# LOCAL_PWR.net
KiCad netlist of a schematic drawn in Altium Designer
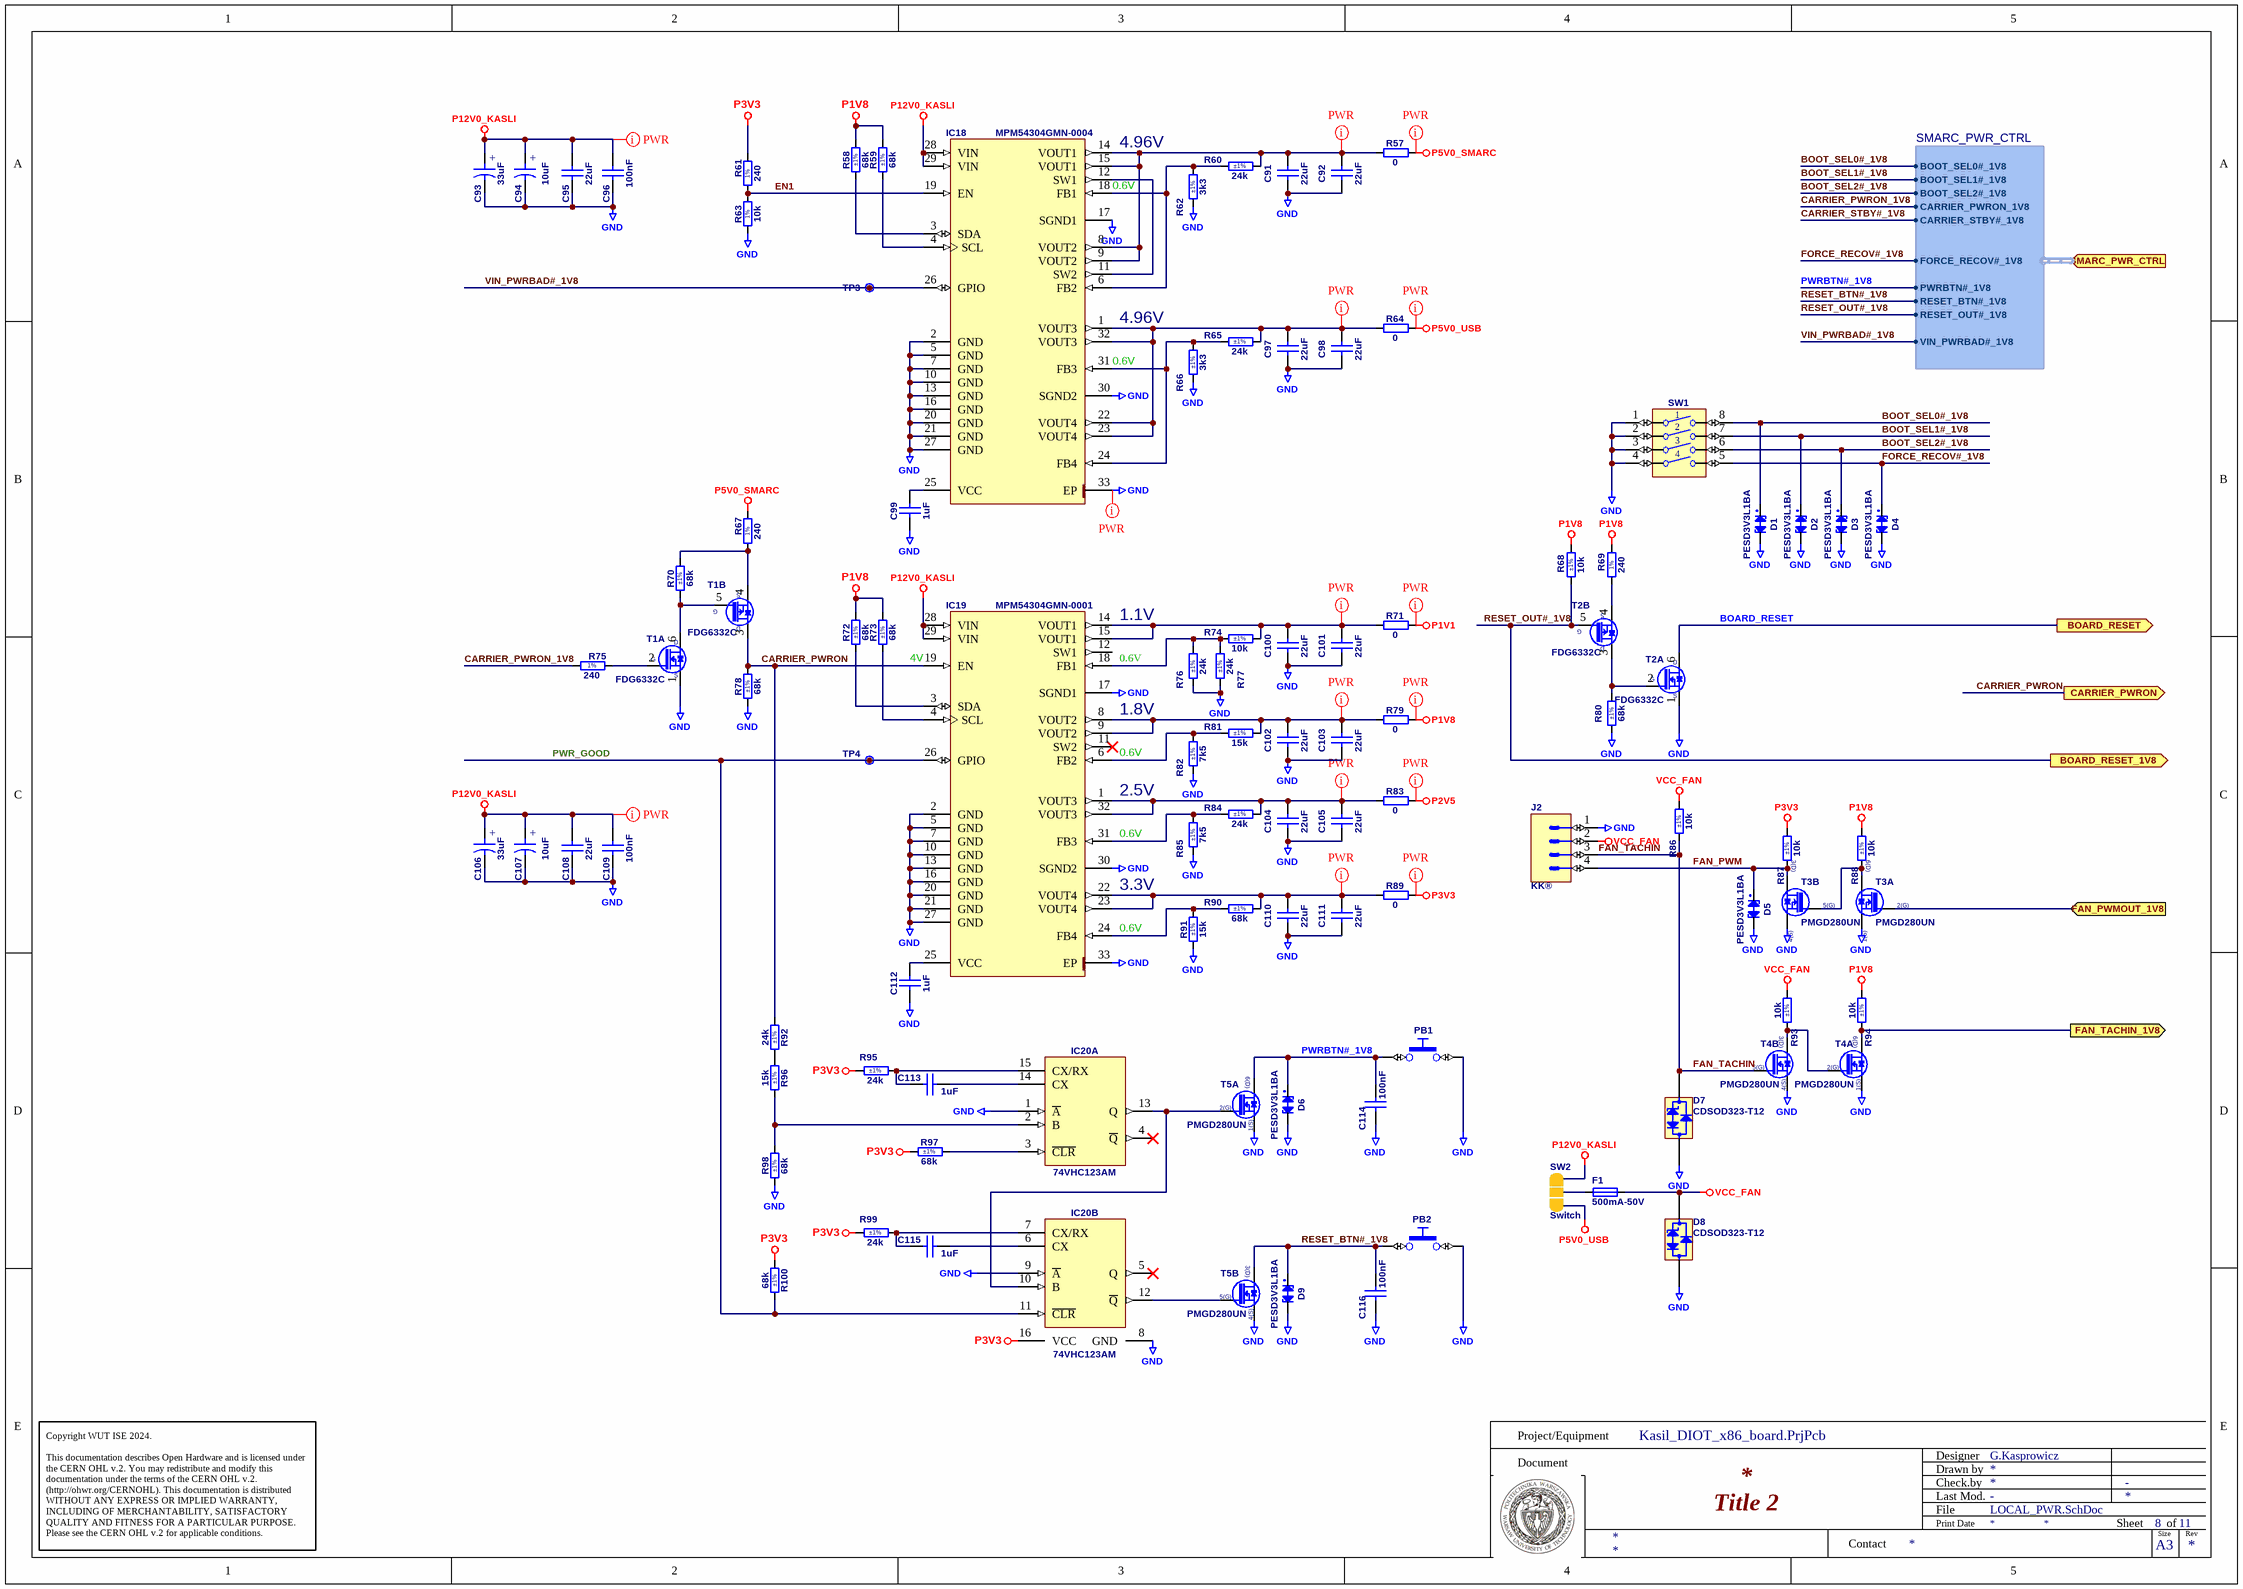
[diagram p0: LOCAL_PWR.SchDoc]

(export (version "E")
  (design (tool "Eeschema 10.0.6"))
  (components
    (comp (ref "C91")
      (value "22uF")
      (footprint "CAPC2012X135N")
      (description "Non-polarised capacitor")
      (fields
        (field (name "MANUFACTURER PART NUMBER") "CC0805_22UF_16V_10%_X5R")
        (field (name "MANUFACTURER") "GENERIC")
        (field (name "AUTHOR") "CERN DEM JLC")
      )
      (libsource (lib "Capacitors") (part "Capacitor - non polarized"))
    )
    (comp (ref "C92")
      (value "22uF")
      (footprint "CAPC2012X135N")
      (description "Non-polarised capacitor")
      (fields
        (field (name "MANUFACTURER PART NUMBER") "CC0805_22UF_16V_10%_X5R")
        (field (name "MANUFACTURER") "GENERIC")
        (field (name "AUTHOR") "CERN DEM JLC")
      )
      (libsource (lib "Capacitors") (part "Capacitor - non polarized"))
    )
    (comp (ref "C93")
      (value "33uF")
      (footprint "CAPMP3528X210N")
      (description "Polarised capacitor")
      (fields
        (field (name "PART NUMBER") "CTE3528-21_33UF_16V_10%")
        (field (name "VOLTAGE") "16V")
        (field (name "AUTHOR") "CERN DEM JLC")
      )
      (libsource (lib "Capacitors") (part "Capacitor - polarized"))
    )
    (comp (ref "C94")
      (value "10uF")
      (footprint "CAPMP3216X180N")
      (description "Polarised capacitor")
      (fields
        (field (name "PART NUMBER") "CTE3216-18_10UF_16V_20%_AVX_TCJ")
        (field (name "VOLTAGE") "16V")
        (field (name "AUTHOR") "CERN DEM JLC")
      )
      (libsource (lib "Capacitors") (part "Capacitor - polarized"))
    )
    (comp (ref "C95")
      (value "22uF")
      (footprint "CAPC2012X135N")
      (description "Non-polarised capacitor")
      (fields
        (field (name "MANUFACTURER PART NUMBER") "CC0805_22UF_16V_10%_X5R")
        (field (name "MANUFACTURER") "GENERIC")
        (field (name "AUTHOR") "CERN DEM JLC")
      )
      (libsource (lib "Capacitors") (part "Capacitor - non polarized"))
    )
    (comp (ref "C96")
      (value "100nF")
      (footprint "CAPC1005X55N")
      (description "Non-polarised capacitor")
      (fields
        (field (name "PART NUMBER") "CC0402_100NF_16V_10%_X7R")
        (field (name "VOLTAGE") "16V")
        (field (name "AUTHOR") "CERN DEM JLC")
      )
      (libsource (lib "Capacitors") (part "Capacitor - non polarized"))
    )
    (comp (ref "C97")
      (value "22uF")
      (footprint "CAPC2012X135N")
      (description "Non-polarised capacitor")
      (fields
        (field (name "MANUFACTURER PART NUMBER") "CC0805_22UF_16V_10%_X5R")
        (field (name "MANUFACTURER") "GENERIC")
        (field (name "AUTHOR") "CERN DEM JLC")
      )
      (libsource (lib "Capacitors") (part "Capacitor - non polarized"))
    )
    (comp (ref "C98")
      (value "22uF")
      (footprint "CAPC2012X135N")
      (description "Non-polarised capacitor")
      (fields
        (field (name "MANUFACTURER PART NUMBER") "CC0805_22UF_16V_10%_X5R")
        (field (name "MANUFACTURER") "GENERIC")
        (field (name "AUTHOR") "CERN DEM JLC")
      )
      (libsource (lib "Capacitors") (part "Capacitor - non polarized"))
    )
    (comp (ref "C99")
      (value "1uF")
      (footprint "CAPC1005X55N")
      (description "Non-polarised capacitor")
      (fields
        (field (name "PART NUMBER") "CC0402_1UF_16V_10%_X5R")
        (field (name "VOLTAGE") "16V")
        (field (name "AUTHOR") "CERN DEM JLC")
      )
      (libsource (lib "Capacitors") (part "Capacitor - non polarized"))
    )
    (comp (ref "C100")
      (value "22uF")
      (footprint "CAPC2012X135N")
      (description "Non-polarised capacitor")
      (fields
        (field (name "MANUFACTURER PART NUMBER") "CC0805_22UF_16V_10%_X5R")
        (field (name "MANUFACTURER") "GENERIC")
        (field (name "AUTHOR") "CERN DEM JLC")
      )
      (libsource (lib "Capacitors") (part "Capacitor - non polarized"))
    )
    (comp (ref "C101")
      (value "22uF")
      (footprint "CAPC2012X135N")
      (description "Non-polarised capacitor")
      (fields
        (field (name "MANUFACTURER PART NUMBER") "CC0805_22UF_16V_10%_X5R")
        (field (name "MANUFACTURER") "GENERIC")
        (field (name "AUTHOR") "CERN DEM JLC")
      )
      (libsource (lib "Capacitors") (part "Capacitor - non polarized"))
    )
    (comp (ref "C102")
      (value "22uF")
      (footprint "CAPC2012X135N")
      (description "Non-polarised capacitor")
      (fields
        (field (name "MANUFACTURER PART NUMBER") "CC0805_22UF_16V_10%_X5R")
        (field (name "MANUFACTURER") "GENERIC")
        (field (name "AUTHOR") "CERN DEM JLC")
      )
      (libsource (lib "Capacitors") (part "Capacitor - non polarized"))
    )
    (comp (ref "C103")
      (value "22uF")
      (footprint "CAPC2012X135N")
      (description "Non-polarised capacitor")
      (fields
        (field (name "MANUFACTURER PART NUMBER") "CC0805_22UF_16V_10%_X5R")
        (field (name "MANUFACTURER") "GENERIC")
        (field (name "AUTHOR") "CERN DEM JLC")
      )
      (libsource (lib "Capacitors") (part "Capacitor - non polarized"))
    )
    (comp (ref "C104")
      (value "22uF")
      (footprint "CAPC2012X135N")
      (description "Non-polarised capacitor")
      (fields
        (field (name "MANUFACTURER PART NUMBER") "CC0805_22UF_16V_10%_X5R")
        (field (name "MANUFACTURER") "GENERIC")
        (field (name "AUTHOR") "CERN DEM JLC")
      )
      (libsource (lib "Capacitors") (part "Capacitor - non polarized"))
    )
    (comp (ref "C105")
      (value "22uF")
      (footprint "CAPC2012X135N")
      (description "Non-polarised capacitor")
      (fields
        (field (name "MANUFACTURER PART NUMBER") "CC0805_22UF_16V_10%_X5R")
        (field (name "MANUFACTURER") "GENERIC")
        (field (name "AUTHOR") "CERN DEM JLC")
      )
      (libsource (lib "Capacitors") (part "Capacitor - non polarized"))
    )
    (comp (ref "C106")
      (value "33uF")
      (footprint "CAPMP3528X210N")
      (description "Polarised capacitor")
      (fields
        (field (name "PART NUMBER") "CTE3528-21_33UF_16V_10%")
        (field (name "VOLTAGE") "16V")
        (field (name "AUTHOR") "CERN DEM JLC")
      )
      (libsource (lib "Capacitors") (part "Capacitor - polarized"))
    )
    (comp (ref "C107")
      (value "10uF")
      (footprint "CAPMP3216X180N")
      (description "Polarised capacitor")
      (fields
        (field (name "PART NUMBER") "CTE3216-18_10UF_16V_20%_AVX_TCJ")
        (field (name "VOLTAGE") "16V")
        (field (name "AUTHOR") "CERN DEM JLC")
      )
      (libsource (lib "Capacitors") (part "Capacitor - polarized"))
    )
    (comp (ref "C108")
      (value "22uF")
      (footprint "CAPC2012X135N")
      (description "Non-polarised capacitor")
      (fields
        (field (name "MANUFACTURER PART NUMBER") "CC0805_22UF_16V_10%_X5R")
        (field (name "MANUFACTURER") "GENERIC")
        (field (name "AUTHOR") "CERN DEM JLC")
      )
      (libsource (lib "Capacitors") (part "Capacitor - non polarized"))
    )
    (comp (ref "C109")
      (value "100nF")
      (footprint "CAPC1005X55N")
      (description "Non-polarised capacitor")
      (fields
        (field (name "PART NUMBER") "CC0402_100NF_16V_10%_X7R")
        (field (name "VOLTAGE") "16V")
        (field (name "AUTHOR") "CERN DEM JLC")
      )
      (libsource (lib "Capacitors") (part "Capacitor - non polarized"))
    )
    (comp (ref "C110")
      (value "22uF")
      (footprint "CAPC2012X135N")
      (description "Non-polarised capacitor")
      (fields
        (field (name "MANUFACTURER PART NUMBER") "CC0805_22UF_16V_10%_X5R")
        (field (name "MANUFACTURER") "GENERIC")
        (field (name "AUTHOR") "CERN DEM JLC")
      )
      (libsource (lib "Capacitors") (part "Capacitor - non polarized"))
    )
    (comp (ref "C111")
      (value "22uF")
      (footprint "CAPC2012X135N")
      (description "Non-polarised capacitor")
      (fields
        (field (name "MANUFACTURER PART NUMBER") "CC0805_22UF_16V_10%_X5R")
        (field (name "MANUFACTURER") "GENERIC")
        (field (name "AUTHOR") "CERN DEM JLC")
      )
      (libsource (lib "Capacitors") (part "Capacitor - non polarized"))
    )
    (comp (ref "C112")
      (value "1uF")
      (footprint "CAPC1005X55N")
      (description "Non-polarised capacitor")
      (fields
        (field (name "PART NUMBER") "CC0402_1UF_16V_10%_X5R")
        (field (name "VOLTAGE") "16V")
        (field (name "AUTHOR") "CERN DEM JLC")
      )
      (libsource (lib "Capacitors") (part "Capacitor - non polarized"))
    )
    (comp (ref "C113")
      (value "1uF")
      (footprint "CAPC1005X55N")
      (description "Non-polarised capacitor")
      (fields
        (field (name "PART NUMBER") "CC0402_1UF_16V_10%_X5R")
        (field (name "VOLTAGE") "16V")
        (field (name "AUTHOR") "CERN DEM JLC")
      )
      (libsource (lib "Capacitors") (part "Capacitor - non polarized"))
    )
    (comp (ref "C114")
      (value "100nF")
      (footprint "CAPC1005X55N")
      (description "Non-polarised capacitor")
      (fields
        (field (name "PART NUMBER") "CC0402_100NF_16V_10%_X7R")
        (field (name "VOLTAGE") "16V")
        (field (name "AUTHOR") "CERN DEM JLC")
      )
      (libsource (lib "Capacitors") (part "Capacitor - non polarized"))
    )
    (comp (ref "C115")
      (value "1uF")
      (footprint "CAPC1005X55N")
      (description "Non-polarised capacitor")
      (fields
        (field (name "PART NUMBER") "CC0402_1UF_16V_10%_X5R")
        (field (name "VOLTAGE") "16V")
        (field (name "AUTHOR") "CERN DEM JLC")
      )
      (libsource (lib "Capacitors") (part "Capacitor - non polarized"))
    )
    (comp (ref "C116")
      (value "100nF")
      (footprint "CAPC1005X55N")
      (description "Non-polarised capacitor")
      (fields
        (field (name "PART NUMBER") "CC0402_100NF_16V_10%_X7R")
        (field (name "VOLTAGE") "16V")
        (field (name "AUTHOR") "CERN DEM JLC")
      )
      (libsource (lib "Capacitors") (part "Capacitor - non polarized"))
    )
    (comp (ref "D1")
      (value "PESD3V3L1BA")
      (footprint "SOD2512X110N")
      (description "Bi-Directional ESD Protection Diode")
      (fields
        (field (name "VOLTAGE") "3V3")
        (field (name "POWER") "500W")
        (field (name "AUTHOR") "CERN DEM JMW")
      )
      (libsource (lib "ICs And Semiconductors") (part "Diode ESD Bi-Directional Dot"))
    )
    (comp (ref "D2")
      (value "PESD3V3L1BA")
      (footprint "SOD2512X110N")
      (description "Bi-Directional ESD Protection Diode")
      (fields
        (field (name "VOLTAGE") "3V3")
        (field (name "POWER") "500W")
        (field (name "AUTHOR") "CERN DEM JMW")
      )
      (libsource (lib "ICs And Semiconductors") (part "Diode ESD Bi-Directional Dot"))
    )
    (comp (ref "D3")
      (value "PESD3V3L1BA")
      (footprint "SOD2512X110N")
      (description "Bi-Directional ESD Protection Diode")
      (fields
        (field (name "VOLTAGE") "3V3")
        (field (name "POWER") "500W")
        (field (name "AUTHOR") "CERN DEM JMW")
      )
      (libsource (lib "ICs And Semiconductors") (part "Diode ESD Bi-Directional Dot"))
    )
    (comp (ref "D4")
      (value "PESD3V3L1BA")
      (footprint "SOD2512X110N")
      (description "Bi-Directional ESD Protection Diode")
      (fields
        (field (name "VOLTAGE") "3V3")
        (field (name "POWER") "500W")
        (field (name "AUTHOR") "CERN DEM JMW")
      )
      (libsource (lib "ICs And Semiconductors") (part "Diode ESD Bi-Directional Dot"))
    )
    (comp (ref "D5")
      (value "PESD3V3L1BA")
      (footprint "SOD2512X110N")
      (description "Bi-Directional ESD Protection Diode")
      (fields
        (field (name "VOLTAGE") "3V3")
        (field (name "POWER") "500W")
        (field (name "AUTHOR") "CERN DEM JMW")
      )
      (libsource (lib "ICs And Semiconductors") (part "Diode ESD Bi-Directional Dot"))
    )
    (comp (ref "D6")
      (value "PESD3V3L1BA")
      (footprint "SOD2512X110N")
      (description "Bi-Directional ESD Protection Diode")
      (fields
        (field (name "VOLTAGE") "3V3")
        (field (name "POWER") "500W")
        (field (name "AUTHOR") "CERN DEM JMW")
      )
      (libsource (lib "ICs And Semiconductors") (part "Diode ESD Bi-Directional Dot"))
    )
    (comp (ref "D7")
      (value "CDSOD323-T12")
      (footprint "SOD2513X114N")
      (description "Unidirectional ESD Protection for Transient Voltage Suppressor Diode")
      (fields
        (field (name "VOLTAGE") "12V")
        (field (name "POWER") "350W")
        (field (name "AUTHOR") "CERN DEM BC")
      )
      (libsource (lib "ICs And Semiconductors") (part "CDSOD323-TXX"))
    )
    (comp (ref "D8")
      (value "CDSOD323-T12")
      (footprint "SOD2513X114N")
      (description "Unidirectional ESD Protection for Transient Voltage Suppressor Diode")
      (fields
        (field (name "VOLTAGE") "12V")
        (field (name "POWER") "350W")
        (field (name "AUTHOR") "CERN DEM BC")
      )
      (libsource (lib "ICs And Semiconductors") (part "CDSOD323-TXX"))
    )
    (comp (ref "D9")
      (value "PESD3V3L1BA")
      (footprint "SOD2512X110N")
      (description "Bi-Directional ESD Protection Diode")
      (fields
        (field (name "VOLTAGE") "3V3")
        (field (name "POWER") "500W")
        (field (name "AUTHOR") "CERN DEM JMW")
      )
      (libsource (lib "ICs And Semiconductors") (part "Diode ESD Bi-Directional Dot"))
    )
    (comp (ref "F1")
      (value "500mA-50V")
      (footprint "FUSC_BOURNS_SF-0603F")
      (description "Fuse")
      (fields
        (field (name "PART NUMBER") "FUS0603_BOURNS-SF-0603F050-2")
        (field (name "MANUFACTURER") "BOURNS")
        (field (name "AUTHOR") "CERN DEM JLC")
      )
      (libsource (lib "Eletro-mechanical") (part "Fuse"))
    )
    (comp (ref "IC18")
      (value "MPM54304GMN-0004")
      (footprint "MPS_MPM54304GMN")
      (description "Quad-Output Power Module with I2C and MTP")
      (fields
        (field (name "PART NUMBER") "MPM54304GMN-002")
        (field (name "MANUFACTURER") "MPS (MONOLITIC  POWER SYSTEMS)")
        (field (name "AUTHOR") "CERN DEM BC")
      )
      (libsource (lib "ICs And Semiconductors") (part "MPM54304GMN"))
    )
    (comp (ref "IC19")
      (value "MPM54304GMN-0001")
      (footprint "MPS_MPM54304GMN")
      (description "Quad-Output Power Module with I2C and MTP")
      (fields
        (field (name "MANUFACTURER") "MPS (MONOLITIC  POWER SYSTEMS)")
        (field (name "MANUFACTURER PART NUMBER") "MPM54304GMN-002")
        (field (name "AUTHOR") "CERN DEM BC")
      )
      (libsource (lib "ICs And Semiconductors") (part "MPM54304GMN"))
    )
    (comp (ref "IC20")
      (value "74VHC123AM")
      (footprint "SOIC127P600X175-16N")
      (description "Retriggerable Monostable Multivibrator")
      (fields (field (name "MANUFACTURER") "FAIRCHILD SEMICONDUCTOR") (field (name "AUTHOR") "CERN DEM BC"))
      (libsource (lib "ICs And Semiconductors") (part "74123"))
    )
    (comp (ref "J2")
      (value "KK®")
      (footprint "MOLEX_22-04-1041")
      (description "Connector 4 Male")
      (fields
        (field (name "PART NUMBER") "MOLEX_22-04-1041")
        (field (name "MANUFACTURER") "MOLEX")
        (field (name "AUTHOR") "CERN DEM JLC")
      )
      (libsource (lib "Connectors") (part "Connector 4 Male"))
    )
    (comp (ref "PB1")
      (value "Push Button")
      (footprint "PB_TYCO_FSMSM")
      (description "Push-Button Switch SPST")
      (fields
        (field (name "PART NUMBER") "PB_TYCO_FSMSM")
        (field (name "MANUFACTURER") "TYCO ELECTRONICS")
        (field (name "AUTHOR") "CERN DEM JLC")
      )
      (libsource (lib "Eletro-mechanical") (part "PB SPST 1NO-2NO"))
    )
    (comp (ref "PB2")
      (value "Push Button")
      (footprint "PB_TYCO_FSMSM")
      (description "Push-Button Switch SPST")
      (fields
        (field (name "PART NUMBER") "PB_TYCO_FSMSM")
        (field (name "MANUFACTURER") "TYCO ELECTRONICS")
        (field (name "AUTHOR") "CERN DEM JLC")
      )
      (libsource (lib "Eletro-mechanical") (part "PB SPST 1NO-2NO"))
    )
    (comp (ref "R57")
      (value "0")
      (footprint "RESC2012X60N")
      (description "Resistor")
      (fields
        (field (name "PART NUMBER") "R0805_0R_JUMPER")
        (field (name "MANUFACTURER") "GENERIC")
        (field (name "AUTHOR") "CERN DEM JLC")
      )
      (libsource (lib "Resistors") (part "Resistor"))
    )
    (comp (ref "R58")
      (value "68k")
      (footprint "RESC1005X40N")
      (description "Resistor - 1%")
      (fields
        (field (name "TOLERANCE") "±1%")
        (field (name "PART NUMBER") "R0402_68K_1%_0.0625W_100PPM")
        (field (name "POWER") "0.0625W")
        (field (name "AUTHOR") "CERN DEM JLC")
      )
      (libsource (lib "Resistors") (part "Resistor - 1%"))
    )
    (comp (ref "R59")
      (value "68k")
      (footprint "RESC1005X40N")
      (description "Resistor - 1%")
      (fields
        (field (name "TOLERANCE") "±1%")
        (field (name "PART NUMBER") "R0402_68K_1%_0.0625W_100PPM")
        (field (name "POWER") "0.0625W")
        (field (name "AUTHOR") "CERN DEM JLC")
      )
      (libsource (lib "Resistors") (part "Resistor - 1%"))
    )
    (comp (ref "R60")
      (value "24k")
      (footprint "RESC1005X40N")
      (description "Resistor - 1%")
      (fields
        (field (name "TOLERANCE") "±1%")
        (field (name "PART NUMBER") "R0402_24K_1%_0.0625W_100PPM")
        (field (name "POWER") "0.0625W")
        (field (name "AUTHOR") "CERN DEM JLC")
      )
      (libsource (lib "Resistors") (part "Resistor - 1%"))
    )
    (comp (ref "R61")
      (value "240")
      (footprint "RESC1005X40N")
      (description "Resistor - 1%")
      (fields
        (field (name "PART NUMBER") "R0402_240R_1%_0.0625W_100PPM")
        (field (name "POWER") "0.0625W")
        (field (name "AUTHOR") "CERN DEM JLC")
      )
      (libsource (lib "Resistors") (part "Resistor - 1%"))
    )
    (comp (ref "R62")
      (value "3k3")
      (footprint "RESC1005X40N")
      (description "Resistor - 1%")
      (fields
        (field (name "TOLERANCE") "±1%")
        (field (name "PART NUMBER") "R0402_3K3_1%_0.0625W_100PPM")
        (field (name "POWER") "0.0625W")
        (field (name "AUTHOR") "CERN DEM JLC")
      )
      (libsource (lib "Resistors") (part "Resistor - 1%"))
    )
    (comp (ref "R63")
      (value "10k")
      (footprint "RESC1005X40N")
      (description "Resistor - 1%")
      (fields
        (field (name "PART NUMBER") "R0402_10K_1%_0.0625W_100PPM")
        (field (name "POWER") "0.0625W")
        (field (name "AUTHOR") "CERN DEM JLC")
      )
      (libsource (lib "Resistors") (part "Resistor - 1%"))
    )
    (comp (ref "R64")
      (value "0")
      (footprint "RESC2012X60N")
      (description "Resistor")
      (fields
        (field (name "PART NUMBER") "R0805_0R_JUMPER")
        (field (name "MANUFACTURER") "GENERIC")
        (field (name "AUTHOR") "CERN DEM JLC")
      )
      (libsource (lib "Resistors") (part "Resistor"))
    )
    (comp (ref "R65")
      (value "24k")
      (footprint "RESC1005X40N")
      (description "Resistor - 1%")
      (fields
        (field (name "TOLERANCE") "±1%")
        (field (name "PART NUMBER") "R0402_24K_1%_0.0625W_100PPM")
        (field (name "POWER") "0.0625W")
        (field (name "AUTHOR") "CERN DEM JLC")
      )
      (libsource (lib "Resistors") (part "Resistor - 1%"))
    )
    (comp (ref "R66")
      (value "3k3")
      (footprint "RESC1005X40N")
      (description "Resistor - 1%")
      (fields
        (field (name "TOLERANCE") "±1%")
        (field (name "PART NUMBER") "R0402_3K3_1%_0.0625W_100PPM")
        (field (name "POWER") "0.0625W")
        (field (name "AUTHOR") "CERN DEM JLC")
      )
      (libsource (lib "Resistors") (part "Resistor - 1%"))
    )
    (comp (ref "R67")
      (value "240")
      (footprint "RESC1005X40N")
      (description "Resistor - 1%")
      (fields
        (field (name "PART NUMBER") "R0402_240R_1%_0.0625W_100PPM")
        (field (name "POWER") "0.0625W")
        (field (name "AUTHOR") "CERN DEM JLC")
      )
      (libsource (lib "Resistors") (part "Resistor - 1%"))
    )
    (comp (ref "R68")
      (value "10k")
      (footprint "RESC1005X40N")
      (description "Resistor - 1%")
      (fields
        (field (name "TOLERANCE") "±1%")
        (field (name "PART NUMBER") "R0402_10K_1%_0.0625W_100PPM")
        (field (name "POWER") "0.0625W")
        (field (name "AUTHOR") "CERN DEM JLC")
      )
      (libsource (lib "Resistors") (part "Resistor - 1%"))
    )
    (comp (ref "R69")
      (value "240")
      (footprint "RESC1005X40N")
      (description "Resistor - 1%")
      (fields
        (field (name "PART NUMBER") "R0402_240R_1%_0.0625W_100PPM")
        (field (name "POWER") "0.0625W")
        (field (name "AUTHOR") "CERN DEM JLC")
      )
      (libsource (lib "Resistors") (part "Resistor - 1%"))
    )
    (comp (ref "R70")
      (value "68k")
      (footprint "RESC1005X40N")
      (description "Resistor - 1%")
      (fields
        (field (name "TOLERANCE") "±1%")
        (field (name "PART NUMBER") "R0402_68K_1%_0.0625W_100PPM")
        (field (name "POWER") "0.0625W")
        (field (name "AUTHOR") "CERN DEM JLC")
      )
      (libsource (lib "Resistors") (part "Resistor - 1%"))
    )
    (comp (ref "R71")
      (value "0")
      (footprint "RESC2012X60N")
      (description "Resistor")
      (fields
        (field (name "PART NUMBER") "R0805_0R_JUMPER")
        (field (name "MANUFACTURER") "GENERIC")
        (field (name "AUTHOR") "CERN DEM JLC")
      )
      (libsource (lib "Resistors") (part "Resistor"))
    )
    (comp (ref "R72")
      (value "68k")
      (footprint "RESC1005X40N")
      (description "Resistor - 1%")
      (fields
        (field (name "TOLERANCE") "±1%")
        (field (name "PART NUMBER") "R0402_68K_1%_0.0625W_100PPM")
        (field (name "POWER") "0.0625W")
        (field (name "AUTHOR") "CERN DEM JLC")
      )
      (libsource (lib "Resistors") (part "Resistor - 1%"))
    )
    (comp (ref "R73")
      (value "68k")
      (footprint "RESC1005X40N")
      (description "Resistor - 1%")
      (fields
        (field (name "TOLERANCE") "±1%")
        (field (name "PART NUMBER") "R0402_68K_1%_0.0625W_100PPM")
        (field (name "POWER") "0.0625W")
        (field (name "AUTHOR") "CERN DEM JLC")
      )
      (libsource (lib "Resistors") (part "Resistor - 1%"))
    )
    (comp (ref "R74")
      (value "10k")
      (footprint "RESC1005X40N")
      (description "Resistor - 1%")
      (fields
        (field (name "TOLERANCE") "±1%")
        (field (name "PART NUMBER") "R0402_10K_1%_0.0625W_100PPM")
        (field (name "POWER") "0.0625W")
        (field (name "AUTHOR") "CERN DEM JLC")
      )
      (libsource (lib "Resistors") (part "Resistor - 1%"))
    )
    (comp (ref "R75")
      (value "240")
      (footprint "RESC1005X40N")
      (description "Resistor - 1%")
      (fields
        (field (name "PART NUMBER") "R0402_240R_1%_0.0625W_100PPM")
        (field (name "POWER") "0.0625W")
        (field (name "AUTHOR") "CERN DEM JLC")
      )
      (libsource (lib "Resistors") (part "Resistor - 1%"))
    )
    (comp (ref "R76")
      (value "24k")
      (footprint "RESC1005X40N")
      (description "Resistor - 1%")
      (fields
        (field (name "TOLERANCE") "±1%")
        (field (name "PART NUMBER") "R0402_24K_1%_0.0625W_100PPM")
        (field (name "POWER") "0.0625W")
        (field (name "AUTHOR") "CERN DEM JLC")
      )
      (libsource (lib "Resistors") (part "Resistor - 1%"))
    )
    (comp (ref "R77")
      (value "24k")
      (footprint "RESC1005X40N")
      (description "Resistor - 1%")
      (fields
        (field (name "TOLERANCE") "±1%")
        (field (name "PART NUMBER") "R0402_24K_1%_0.0625W_100PPM")
        (field (name "POWER") "0.0625W")
        (field (name "AUTHOR") "CERN DEM JLC")
      )
      (libsource (lib "Resistors") (part "Resistor - 1%"))
    )
    (comp (ref "R78")
      (value "68k")
      (footprint "RESC1005X40N")
      (description "Resistor - 1%")
      (fields
        (field (name "TOLERANCE") "±1%")
        (field (name "PART NUMBER") "R0402_68K_1%_0.0625W_100PPM")
        (field (name "POWER") "0.0625W")
        (field (name "AUTHOR") "CERN DEM JLC")
      )
      (libsource (lib "Resistors") (part "Resistor - 1%"))
    )
    (comp (ref "R79")
      (value "0")
      (footprint "RESC2012X60N")
      (description "Resistor")
      (fields
        (field (name "PART NUMBER") "R0805_0R_JUMPER")
        (field (name "MANUFACTURER") "GENERIC")
        (field (name "AUTHOR") "CERN DEM JLC")
      )
      (libsource (lib "Resistors") (part "Resistor"))
    )
    (comp (ref "R80")
      (value "68k")
      (footprint "RESC1005X40N")
      (description "Resistor - 1%")
      (fields
        (field (name "TOLERANCE") "±1%")
        (field (name "PART NUMBER") "R0402_68K_1%_0.0625W_100PPM")
        (field (name "POWER") "0.0625W")
        (field (name "AUTHOR") "CERN DEM JLC")
      )
      (libsource (lib "Resistors") (part "Resistor - 1%"))
    )
    (comp (ref "R81")
      (value "15k")
      (footprint "RESC1005X40N")
      (description "Resistor - 1%")
      (fields
        (field (name "TOLERANCE") "±1%")
        (field (name "PART NUMBER") "R0402_15K_1%_0.0625W_100PPM")
        (field (name "POWER") "0.0625W")
        (field (name "AUTHOR") "CERN DEM JMW")
      )
      (libsource (lib "Resistors") (part "Resistor - 1%"))
    )
    (comp (ref "R82")
      (value "7k5")
      (footprint "RESC1005X40N")
      (description "Resistor - 1%")
      (fields
        (field (name "TOLERANCE") "±1%")
        (field (name "PART NUMBER") "R0402_7K5_1%_0.0625W_100PPM")
        (field (name "POWER") "0.0625W")
        (field (name "AUTHOR") "CERN DEM JLC")
      )
      (libsource (lib "Resistors") (part "Resistor - 1%"))
    )
    (comp (ref "R83")
      (value "0")
      (footprint "RESC2012X60N")
      (description "Resistor")
      (fields
        (field (name "PART NUMBER") "R0805_0R_JUMPER")
        (field (name "MANUFACTURER") "GENERIC")
        (field (name "AUTHOR") "CERN DEM JLC")
      )
      (libsource (lib "Resistors") (part "Resistor"))
    )
    (comp (ref "R84")
      (value "24k")
      (footprint "RESC1005X40N")
      (description "Resistor - 1%")
      (fields
        (field (name "TOLERANCE") "±1%")
        (field (name "PART NUMBER") "R0402_24K_1%_0.0625W_100PPM")
        (field (name "POWER") "0.0625W")
        (field (name "AUTHOR") "CERN DEM JLC")
      )
      (libsource (lib "Resistors") (part "Resistor - 1%"))
    )
    (comp (ref "R85")
      (value "7k5")
      (footprint "RESC1005X40N")
      (description "Resistor - 1%")
      (fields
        (field (name "TOLERANCE") "±1%")
        (field (name "PART NUMBER") "R0402_7K5_1%_0.0625W_100PPM")
        (field (name "POWER") "0.0625W")
        (field (name "AUTHOR") "CERN DEM JLC")
      )
      (libsource (lib "Resistors") (part "Resistor - 1%"))
    )
    (comp (ref "R86")
      (value "10k")
      (footprint "RESC1005X40N")
      (description "Resistor - 1%")
      (fields
        (field (name "TOLERANCE") "±1%")
        (field (name "PART NUMBER") "R0402_10K_1%_0.0625W_100PPM")
        (field (name "POWER") "0.0625W")
        (field (name "AUTHOR") "CERN DEM JLC")
      )
      (libsource (lib "Resistors") (part "Resistor - 1%"))
    )
    (comp (ref "R87")
      (value "10k")
      (footprint "RESC1005X40N")
      (description "Resistor - 1%")
      (fields
        (field (name "TOLERANCE") "±1%")
        (field (name "PART NUMBER") "R0402_10K_1%_0.0625W_100PPM")
        (field (name "POWER") "0.0625W")
        (field (name "AUTHOR") "CERN DEM JLC")
      )
      (libsource (lib "Resistors") (part "Resistor - 1%"))
    )
    (comp (ref "R88")
      (value "10k")
      (footprint "RESC1005X40N")
      (description "Resistor - 1%")
      (fields
        (field (name "TOLERANCE") "±1%")
        (field (name "PART NUMBER") "R0402_10K_1%_0.0625W_100PPM")
        (field (name "POWER") "0.0625W")
        (field (name "AUTHOR") "CERN DEM JLC")
      )
      (libsource (lib "Resistors") (part "Resistor - 1%"))
    )
    (comp (ref "R89")
      (value "0")
      (footprint "RESC2012X60N")
      (description "Resistor")
      (fields
        (field (name "PART NUMBER") "R0805_0R_JUMPER")
        (field (name "MANUFACTURER") "GENERIC")
        (field (name "AUTHOR") "CERN DEM JLC")
      )
      (libsource (lib "Resistors") (part "Resistor"))
    )
    (comp (ref "R90")
      (value "68k")
      (footprint "RESC1005X40N")
      (description "Resistor - 1%")
      (fields
        (field (name "TOLERANCE") "±1%")
        (field (name "PART NUMBER") "R0402_68K_1%_0.0625W_100PPM")
        (field (name "POWER") "0.0625W")
        (field (name "AUTHOR") "CERN DEM JLC")
      )
      (libsource (lib "Resistors") (part "Resistor - 1%"))
    )
    (comp (ref "R91")
      (value "15k")
      (footprint "RESC1005X40N")
      (description "Resistor - 1%")
      (fields
        (field (name "TOLERANCE") "±1%")
        (field (name "PART NUMBER") "R0402_15K_1%_0.0625W_100PPM")
        (field (name "POWER") "0.0625W")
        (field (name "AUTHOR") "CERN DEM JMW")
      )
      (libsource (lib "Resistors") (part "Resistor - 1%"))
    )
    (comp (ref "R92")
      (value "24k")
      (footprint "RESC1005X40N")
      (description "Resistor - 1%")
      (fields
        (field (name "TOLERANCE") "±1%")
        (field (name "PART NUMBER") "R0402_24K_1%_0.0625W_100PPM")
        (field (name "POWER") "0.0625W")
        (field (name "AUTHOR") "CERN DEM JLC")
      )
      (libsource (lib "Resistors") (part "Resistor - 1%"))
    )
    (comp (ref "R93")
      (value "10k")
      (footprint "RESC1005X40N")
      (description "Resistor - 1%")
      (fields
        (field (name "TOLERANCE") "±1%")
        (field (name "PART NUMBER") "R0402_10K_1%_0.0625W_100PPM")
        (field (name "POWER") "0.0625W")
        (field (name "AUTHOR") "CERN DEM JLC")
      )
      (libsource (lib "Resistors") (part "Resistor - 1%"))
    )
    (comp (ref "R94")
      (value "10k")
      (footprint "RESC1005X40N")
      (description "Resistor - 1%")
      (fields
        (field (name "TOLERANCE") "±1%")
        (field (name "PART NUMBER") "R0402_10K_1%_0.0625W_100PPM")
        (field (name "POWER") "0.0625W")
        (field (name "AUTHOR") "CERN DEM JLC")
      )
      (libsource (lib "Resistors") (part "Resistor - 1%"))
    )
    (comp (ref "R95")
      (value "24k")
      (footprint "RESC1005X40N")
      (description "Resistor - 1%")
      (fields
        (field (name "TOLERANCE") "±1%")
        (field (name "PART NUMBER") "R0402_24K_1%_0.0625W_100PPM")
        (field (name "POWER") "0.0625W")
        (field (name "AUTHOR") "CERN DEM JLC")
      )
      (libsource (lib "Resistors") (part "Resistor - 1%"))
    )
    (comp (ref "R96")
      (value "15k")
      (footprint "RESC1005X40N")
      (description "Resistor - 1%")
      (fields
        (field (name "TOLERANCE") "±1%")
        (field (name "PART NUMBER") "R0402_15K_1%_0.0625W_100PPM")
        (field (name "POWER") "0.0625W")
        (field (name "AUTHOR") "CERN DEM JMW")
      )
      (libsource (lib "Resistors") (part "Resistor - 1%"))
    )
    (comp (ref "R97")
      (value "68k")
      (footprint "RESC1005X40N")
      (description "Resistor - 1%")
      (fields
        (field (name "TOLERANCE") "±1%")
        (field (name "PART NUMBER") "R0402_68K_1%_0.0625W_100PPM")
        (field (name "POWER") "0.0625W")
        (field (name "AUTHOR") "CERN DEM JLC")
      )
      (libsource (lib "Resistors") (part "Resistor - 1%"))
    )
    (comp (ref "R98")
      (value "68k")
      (footprint "RESC1005X40N")
      (description "Resistor - 1%")
      (fields
        (field (name "TOLERANCE") "±1%")
        (field (name "PART NUMBER") "R0402_68K_1%_0.0625W_100PPM")
        (field (name "POWER") "0.0625W")
        (field (name "AUTHOR") "CERN DEM JLC")
      )
      (libsource (lib "Resistors") (part "Resistor - 1%"))
    )
    (comp (ref "R99")
      (value "24k")
      (footprint "RESC1005X40N")
      (description "Resistor - 1%")
      (fields
        (field (name "TOLERANCE") "±1%")
        (field (name "PART NUMBER") "R0402_24K_1%_0.0625W_100PPM")
        (field (name "POWER") "0.0625W")
        (field (name "AUTHOR") "CERN DEM JLC")
      )
      (libsource (lib "Resistors") (part "Resistor - 1%"))
    )
    (comp (ref "R100")
      (value "68k")
      (footprint "RESC1005X40N")
      (description "Resistor - 1%")
      (fields
        (field (name "TOLERANCE") "±1%")
        (field (name "PART NUMBER") "R0402_68K_1%_0.0625W_100PPM")
        (field (name "POWER") "0.0625W")
        (field (name "AUTHOR") "CERN DEM JLC")
      )
      (libsource (lib "Resistors") (part "Resistor - 1%"))
    )
    (comp (ref "SW1")
      (value "Switch")
      (footprint "SW_DIPTRONICS_DHA-04TQ")
      (description "4 Ways SPST DIP Switch")
      (fields
        (field (name "PART NUMBER") "SW_DIPTRONICS_DHA-04TQ")
        (field (name "MANUFACTURER") "DIPTRONICS")
        (field (name "AUTHOR") "CERN DEM JLC")
      )
      (libsource (lib "Eletro-mechanical") (part "SW 4x SPST DIP Switch"))
    )
    (comp (ref "SW2")
      (value "Switch")
      (footprint "JUMPSM3P")
      (description "3 SMD Pads for Bound by Solder  Drop")
      (fields
        (field (name "PART NUMBER") "JUMPSM3P")
        (field (name "MANUFACTURER") "None")
        (field (name "AUTHOR") "CERN DEM JLC")
      )
      (libsource (lib "Eletro-mechanical") (part "SMD Solder Jumper 3 Pads"))
    )
    (comp (ref "T1")
      (value "FDG6332C")
      (footprint "SOT65P210X110-6N")
      (description "20V N & P-Channel PowerTrench MOSFETs")
      (fields (field (name "MANUFACTURER") "FAIRCHILD SEMICONDUCTOR") (field (name "AUTHOR") "CERN DEM JLC"))
      (libsource (lib "ICs And Semiconductors") (part "FDG6332C"))
    )
    (comp (ref "T2")
      (value "FDG6332C")
      (footprint "SOT65P210X110-6N")
      (description "20V N & P-Channel PowerTrench MOSFETs")
      (fields (field (name "MANUFACTURER") "FAIRCHILD SEMICONDUCTOR") (field (name "AUTHOR") "CERN DEM JLC"))
      (libsource (lib "ICs And Semiconductors") (part "FDG6332C"))
    )
    (comp (ref "T3")
      (value "PMGD280UN")
      (footprint "SOT65P210X110-6N")
      (description "Dual N-Channel micro TrenchMOS™ Ultra Low Level FET")
      (fields (field (name "MANUFACTURER") "NXP SEMICONDUCTORS") (field (name "AUTHOR") "CERN DEM JLC"))
      (libsource (lib "") (part "PMGD280UN_3"))
    )
    (comp (ref "T4")
      (value "PMGD280UN")
      (footprint "SOT65P210X110-6N")
      (description "Dual N-Channel micro TrenchMOS™ Ultra Low Level FET")
      (fields (field (name "MANUFACTURER") "NXP SEMICONDUCTORS") (field (name "AUTHOR") "CERN DEM JLC"))
      (libsource (lib "") (part "PMGD280UN_2"))
    )
    (comp (ref "T5")
      (value "PMGD280UN")
      (footprint "SOT65P210X110-6N")
      (description "Dual N-Channel micro TrenchMOS™ Ultra Low Level FET")
      (fields (field (name "MANUFACTURER") "NXP SEMICONDUCTORS") (field (name "AUTHOR") "CERN DEM JLC"))
      (libsource (lib "") (part "PMGD280UN_1"))
    )
    (comp (ref "TP3")
      (value "Test Point")
      (footprint "TPS127")
      (fields (field (name "PART NUMBER") "SMD_PAD_1.27X1.27MM") (field (name "AUTHOR") "CERN DEM JLC"))
      (libsource (lib "Eletro-mechanical") (part "Test Point"))
    )
    (comp (ref "TP4")
      (value "Test Point")
      (footprint "TPS127")
      (fields (field (name "PART NUMBER") "SMD_PAD_1.27X1.27MM") (field (name "AUTHOR") "CERN DEM JLC"))
      (libsource (lib "Eletro-mechanical") (part "Test Point"))
    )
  )
  (nets
    (net (code "2") (name "/BOARD_RESET") (class "Default")
      (node (ref "T2") (pin "6") (pinfunction "D_6") (pintype "passive"))
    )
    (net (code "3") (name "/BOOT_SEL0#_1V8") (class "Default")
      (node (ref "D1") (pin "1") (pinfunction "C_1") (pintype "passive"))
      (node (ref "SW1") (pin "8") (pinfunction "8_8") (pintype "bidirectional"))
    )
    (net (code "4") (name "/BOOT_SEL1#_1V8") (class "Default")
      (node (ref "D2") (pin "1") (pinfunction "C_1") (pintype "passive"))
      (node (ref "SW1") (pin "7") (pinfunction "7_7") (pintype "bidirectional"))
    )
    (net (code "5") (name "/BOOT_SEL2#_1V8") (class "Default")
      (node (ref "D3") (pin "1") (pinfunction "C_1") (pintype "passive"))
      (node (ref "SW1") (pin "6") (pinfunction "6_6") (pintype "bidirectional"))
    )
    (net (code "6") (name "/CARRIER_PWRON") (class "Default")
      (node (ref "IC19") (pin "19") (pinfunction "EN_19") (pintype "input"))
      (node (ref "R78") (pin "2") (pinfunction "2_2") (pintype "passive"))
      (node (ref "R92") (pin "1") (pinfunction "1_1") (pintype "passive"))
      (node (ref "T1") (pin "3") (pinfunction "D_3") (pintype "passive"))
    )
    (net (code "7") (name "/CARRIER_PWRON_1V8") (class "Default")
      (node (ref "R75") (pin "1") (pinfunction "1_1") (pintype "passive"))
    )
    (net (code "9") (name "/EN1") (class "Default")
      (node (ref "IC18") (pin "19") (pinfunction "EN_19") (pintype "input"))
      (node (ref "R61") (pin "1") (pinfunction "1_1") (pintype "passive"))
      (node (ref "R63") (pin "2") (pinfunction "2_2") (pintype "passive"))
    )
    (net (code "10") (name "/FAN_PWM") (class "Default")
      (node (ref "D5") (pin "1") (pinfunction "C_1") (pintype "passive"))
      (node (ref "J2") (pin "4") (pinfunction "4_4") (pintype "bidirectional"))
      (node (ref "R87") (pin "1") (pinfunction "1_1") (pintype "passive"))
      (node (ref "T3") (pin "3") (pinfunction "D_3") (pintype "passive"))
    )
    (net (code "11") (name "/FAN_PWMOUT_1V8") (class "Default")
      (node (ref "T3") (pin "2") (pinfunction "G_2") (pintype "passive"))
    )
    (net (code "12") (name "/FAN_TACHIN") (class "Default")
      (node (ref "D7") (pin "1") (pinfunction "C_1") (pintype "passive"))
      (node (ref "J2") (pin "3") (pinfunction "3_3") (pintype "bidirectional"))
      (node (ref "R86") (pin "1") (pinfunction "1_1") (pintype "passive"))
      (node (ref "T4") (pin "5") (pinfunction "G_5") (pintype "passive"))
    )
    (net (code "13") (name "/FAN_TACHIN_1V8") (class "Default")
      (node (ref "R94") (pin "1") (pinfunction "1_1") (pintype "passive"))
      (node (ref "T4") (pin "6") (pinfunction "D_6") (pintype "passive"))
    )
    (net (code "14") (name "/FORCE_RECOV#_1V8") (class "Default")
      (node (ref "D4") (pin "1") (pinfunction "C_1") (pintype "passive"))
      (node (ref "SW1") (pin "5") (pinfunction "5_5") (pintype "bidirectional"))
    )
    (net (code "15") (name "/PWRBTN#_1V8") (class "Default")
      (node (ref "C114") (pin "2") (pinfunction "2_2") (pintype "passive"))
      (node (ref "D6") (pin "1") (pinfunction "C_1") (pintype "passive"))
      (node (ref "PB1") (pin "1") (pinfunction "1_1") (pintype "bidirectional"))
      (node (ref "T5") (pin "6") (pinfunction "D_6") (pintype "passive"))
    )
    (net (code "16") (name "/PWR_GOOD") (class "Default")
      (node (ref "IC19") (pin "26") (pinfunction "GPIO_26") (pintype "bidirectional"))
      (node (ref "IC20") (pin "11") (pinfunction "~{CLR}_11") (pintype "input"))
      (node (ref "R100") (pin "2") (pinfunction "2_2") (pintype "passive"))
      (node (ref "TP4") (pin "1") (pinfunction "1_1") (pintype "bidirectional"))
    )
    (net (code "17") (name "/RESET_BTN#_1V8") (class "Default")
      (node (ref "C116") (pin "2") (pinfunction "2_2") (pintype "passive"))
      (node (ref "D9") (pin "1") (pinfunction "C_1") (pintype "passive"))
      (node (ref "PB2") (pin "1") (pinfunction "1_1") (pintype "bidirectional"))
      (node (ref "T5") (pin "3") (pinfunction "D_3") (pintype "passive"))
    )
    (net (code "18") (name "/RESET_OUT#_1V8") (class "Default")
      (node (ref "R68") (pin "1") (pinfunction "1_1") (pintype "passive"))
      (node (ref "T2") (pin "5") (pinfunction "G_5") (pintype "passive"))
    )
    (net (code "19") (name "/VIN_PWRBAD#_1V8") (class "Default")
      (node (ref "IC18") (pin "26") (pinfunction "GPIO_26") (pintype "bidirectional"))
      (node (ref "TP3") (pin "1") (pinfunction "1_1") (pintype "bidirectional"))
    )
    (net (code "21") (name "GND") (class "Default")
      (node (ref "C100") (pin "1") (pinfunction "1_1") (pintype "passive"))
      (node (ref "C101") (pin "1") (pinfunction "1_1") (pintype "passive"))
      (node (ref "C102") (pin "1") (pinfunction "1_1") (pintype "passive"))
      (node (ref "C103") (pin "1") (pinfunction "1_1") (pintype "passive"))
      (node (ref "C104") (pin "1") (pinfunction "1_1") (pintype "passive"))
      (node (ref "C105") (pin "1") (pinfunction "1_1") (pintype "passive"))
      (node (ref "C106") (pin "2") (pinfunction "2_2") (pintype "passive"))
      (node (ref "C107") (pin "2") (pinfunction "2_2") (pintype "passive"))
      (node (ref "C108") (pin "1") (pinfunction "1_1") (pintype "passive"))
      (node (ref "C109") (pin "1") (pinfunction "1_1") (pintype "passive"))
      (node (ref "C110") (pin "1") (pinfunction "1_1") (pintype "passive"))
      (node (ref "C111") (pin "1") (pinfunction "1_1") (pintype "passive"))
      (node (ref "C112") (pin "1") (pinfunction "1_1") (pintype "passive"))
      (node (ref "C114") (pin "1") (pinfunction "1_1") (pintype "passive"))
      (node (ref "C116") (pin "1") (pinfunction "1_1") (pintype "passive"))
      (node (ref "C91") (pin "1") (pinfunction "1_1") (pintype "passive"))
      (node (ref "C92") (pin "1") (pinfunction "1_1") (pintype "passive"))
      (node (ref "C93") (pin "2") (pinfunction "2_2") (pintype "passive"))
      (node (ref "C94") (pin "2") (pinfunction "2_2") (pintype "passive"))
      (node (ref "C95") (pin "1") (pinfunction "1_1") (pintype "passive"))
      (node (ref "C96") (pin "1") (pinfunction "1_1") (pintype "passive"))
      (node (ref "C97") (pin "1") (pinfunction "1_1") (pintype "passive"))
      (node (ref "C98") (pin "1") (pinfunction "1_1") (pintype "passive"))
      (node (ref "C99") (pin "1") (pinfunction "1_1") (pintype "passive"))
      (node (ref "D1") (pin "2") (pinfunction "C_2") (pintype "passive"))
      (node (ref "D2") (pin "2") (pinfunction "C_2") (pintype "passive"))
      (node (ref "D3") (pin "2") (pinfunction "C_2") (pintype "passive"))
      (node (ref "D4") (pin "2") (pinfunction "C_2") (pintype "passive"))
      (node (ref "D5") (pin "2") (pinfunction "C_2") (pintype "passive"))
      (node (ref "D6") (pin "2") (pinfunction "C_2") (pintype "passive"))
      (node (ref "D7") (pin "2") (pinfunction "A_2") (pintype "passive"))
      (node (ref "D8") (pin "2") (pinfunction "A_2") (pintype "passive"))
      (node (ref "D9") (pin "2") (pinfunction "C_2") (pintype "passive"))
      (node (ref "IC18") (pin "10") (pinfunction "GND_10") (pintype "power_in"))
      (node (ref "IC18") (pin "13") (pinfunction "GND_13") (pintype "power_in"))
      (node (ref "IC18") (pin "16") (pinfunction "GND_16") (pintype "power_in"))
      (node (ref "IC18") (pin "17") (pinfunction "SGND1_17") (pintype "power_in"))
      (node (ref "IC18") (pin "2") (pinfunction "GND_2") (pintype "power_in"))
      (node (ref "IC18") (pin "20") (pinfunction "GND_20") (pintype "power_in"))
      (node (ref "IC18") (pin "21") (pinfunction "GND_21") (pintype "power_in"))
      (node (ref "IC18") (pin "27") (pinfunction "GND_27") (pintype "power_in"))
      (node (ref "IC18") (pin "30") (pinfunction "SGND2_30") (pintype "power_in"))
      (node (ref "IC18") (pin "33") (pinfunction "EP_33") (pintype "power_in"))
      (node (ref "IC18") (pin "5") (pinfunction "GND_5") (pintype "power_in"))
      (node (ref "IC18") (pin "7") (pinfunction "GND_7") (pintype "power_in"))
      (node (ref "IC19") (pin "10") (pinfunction "GND_10") (pintype "power_in"))
      (node (ref "IC19") (pin "13") (pinfunction "GND_13") (pintype "power_in"))
      (node (ref "IC19") (pin "16") (pinfunction "GND_16") (pintype "power_in"))
      (node (ref "IC19") (pin "17") (pinfunction "SGND1_17") (pintype "power_in"))
      (node (ref "IC19") (pin "2") (pinfunction "GND_2") (pintype "power_in"))
      (node (ref "IC19") (pin "20") (pinfunction "GND_20") (pintype "power_in"))
      (node (ref "IC19") (pin "21") (pinfunction "GND_21") (pintype "power_in"))
      (node (ref "IC19") (pin "27") (pinfunction "GND_27") (pintype "power_in"))
      (node (ref "IC19") (pin "30") (pinfunction "SGND2_30") (pintype "power_in"))
      (node (ref "IC19") (pin "33") (pinfunction "EP_33") (pintype "power_in"))
      (node (ref "IC19") (pin "5") (pinfunction "GND_5") (pintype "power_in"))
      (node (ref "IC19") (pin "7") (pinfunction "GND_7") (pintype "power_in"))
      (node (ref "IC20") (pin "1") (pinfunction "~{A}_1") (pintype "input"))
      (node (ref "IC20") (pin "8") (pinfunction "GND_8") (pintype "power_in"))
      (node (ref "IC20") (pin "9") (pinfunction "~{A}_9") (pintype "input"))
      (node (ref "J2") (pin "1") (pinfunction "1_1") (pintype "bidirectional"))
      (node (ref "PB1") (pin "2") (pinfunction "2_2") (pintype "bidirectional"))
      (node (ref "PB2") (pin "2") (pinfunction "2_2") (pintype "bidirectional"))
      (node (ref "R62") (pin "1") (pinfunction "1_1") (pintype "passive"))
      (node (ref "R63") (pin "1") (pinfunction "1_1") (pintype "passive"))
      (node (ref "R66") (pin "1") (pinfunction "1_1") (pintype "passive"))
      (node (ref "R76") (pin "1") (pinfunction "1_1") (pintype "passive"))
      (node (ref "R77") (pin "1") (pinfunction "1_1") (pintype "passive"))
      (node (ref "R78") (pin "1") (pinfunction "1_1") (pintype "passive"))
      (node (ref "R80") (pin "1") (pinfunction "1_1") (pintype "passive"))
      (node (ref "R82") (pin "1") (pinfunction "1_1") (pintype "passive"))
      (node (ref "R85") (pin "1") (pinfunction "1_1") (pintype "passive"))
      (node (ref "R91") (pin "1") (pinfunction "1_1") (pintype "passive"))
      (node (ref "R98") (pin "1") (pinfunction "1_1") (pintype "passive"))
      (node (ref "SW1") (pin "1") (pinfunction "1_1") (pintype "bidirectional"))
      (node (ref "SW1") (pin "2") (pinfunction "2_2") (pintype "bidirectional"))
      (node (ref "SW1") (pin "3") (pinfunction "3_3") (pintype "bidirectional"))
      (node (ref "SW1") (pin "4") (pinfunction "4_4") (pintype "bidirectional"))
      (node (ref "T1") (pin "1") (pinfunction "S_1") (pintype "passive"))
      (node (ref "T2") (pin "1") (pinfunction "S_1") (pintype "passive"))
      (node (ref "T3") (pin "1") (pinfunction "S_1") (pintype "passive"))
      (node (ref "T3") (pin "4") (pinfunction "S_4") (pintype "passive"))
      (node (ref "T4") (pin "1") (pinfunction "S_1") (pintype "passive"))
      (node (ref "T4") (pin "4") (pinfunction "S_4") (pintype "passive"))
      (node (ref "T5") (pin "1") (pinfunction "S_1") (pintype "passive"))
      (node (ref "T5") (pin "4") (pinfunction "S_4") (pintype "passive"))
    )
    (net (code "22") (name "Net-(C91-Pad2)") (class "Default")
      (node (ref "C91") (pin "2") (pinfunction "2_2") (pintype "passive"))
      (node (ref "C92") (pin "2") (pinfunction "2_2") (pintype "passive"))
      (node (ref "IC18") (pin "14") (pinfunction "VOUT1_14") (pintype "output"))
      (node (ref "IC18") (pin "15") (pinfunction "VOUT1_15") (pintype "output"))
      (node (ref "IC18") (pin "8") (pinfunction "VOUT2_8") (pintype "output"))
      (node (ref "IC18") (pin "9") (pinfunction "VOUT2_9") (pintype "output"))
      (node (ref "R57") (pin "1") (pinfunction "1_1") (pintype "passive"))
      (node (ref "R60") (pin "2") (pinfunction "2_2") (pintype "passive"))
    )
    (net (code "23") (name "Net-(C97-Pad2)") (class "Default")
      (node (ref "C97") (pin "2") (pinfunction "2_2") (pintype "passive"))
      (node (ref "C98") (pin "2") (pinfunction "2_2") (pintype "passive"))
      (node (ref "IC18") (pin "1") (pinfunction "VOUT3_1") (pintype "output"))
      (node (ref "IC18") (pin "22") (pinfunction "VOUT4_22") (pintype "output"))
      (node (ref "IC18") (pin "23") (pinfunction "VOUT4_23") (pintype "output"))
      (node (ref "IC18") (pin "32") (pinfunction "VOUT3_32") (pintype "output"))
      (node (ref "R64") (pin "1") (pinfunction "1_1") (pintype "passive"))
      (node (ref "R65") (pin "2") (pinfunction "2_2") (pintype "passive"))
    )
    (net (code "24") (name "Net-(C100-Pad2)") (class "Default")
      (node (ref "C100") (pin "2") (pinfunction "2_2") (pintype "passive"))
      (node (ref "C101") (pin "2") (pinfunction "2_2") (pintype "passive"))
      (node (ref "IC19") (pin "14") (pinfunction "VOUT1_14") (pintype "output"))
      (node (ref "IC19") (pin "15") (pinfunction "VOUT1_15") (pintype "output"))
      (node (ref "R71") (pin "1") (pinfunction "1_1") (pintype "passive"))
      (node (ref "R74") (pin "2") (pinfunction "2_2") (pintype "passive"))
    )
    (net (code "25") (name "Net-(C102-Pad2)") (class "Default")
      (node (ref "C102") (pin "2") (pinfunction "2_2") (pintype "passive"))
      (node (ref "C103") (pin "2") (pinfunction "2_2") (pintype "passive"))
      (node (ref "IC19") (pin "8") (pinfunction "VOUT2_8") (pintype "output"))
      (node (ref "IC19") (pin "9") (pinfunction "VOUT2_9") (pintype "output"))
      (node (ref "R79") (pin "1") (pinfunction "1_1") (pintype "passive"))
      (node (ref "R81") (pin "2") (pinfunction "2_2") (pintype "passive"))
    )
    (net (code "26") (name "Net-(C104-Pad2)") (class "Default")
      (node (ref "C104") (pin "2") (pinfunction "2_2") (pintype "passive"))
      (node (ref "C105") (pin "2") (pinfunction "2_2") (pintype "passive"))
      (node (ref "IC19") (pin "1") (pinfunction "VOUT3_1") (pintype "output"))
      (node (ref "IC19") (pin "32") (pinfunction "VOUT3_32") (pintype "output"))
      (node (ref "R83") (pin "1") (pinfunction "1_1") (pintype "passive"))
      (node (ref "R84") (pin "2") (pinfunction "2_2") (pintype "passive"))
    )
    (net (code "27") (name "Net-(C110-Pad2)") (class "Default")
      (node (ref "C110") (pin "2") (pinfunction "2_2") (pintype "passive"))
      (node (ref "C111") (pin "2") (pinfunction "2_2") (pintype "passive"))
      (node (ref "IC19") (pin "22") (pinfunction "VOUT4_22") (pintype "output"))
      (node (ref "IC19") (pin "23") (pinfunction "VOUT4_23") (pintype "output"))
      (node (ref "R89") (pin "1") (pinfunction "1_1") (pintype "passive"))
      (node (ref "R90") (pin "2") (pinfunction "2_2") (pintype "passive"))
    )
    (net (code "28") (name "Net-(F1-Pad1)") (class "Default")
      (node (ref "F1") (pin "1") (pinfunction "1_1") (pintype "passive"))
      (node (ref "SW2") (pin "2") (pinfunction "2_2") (pintype "bidirectional"))
    )
    (net (code "29") (name "Net-(IC18-FB1)") (class "Default")
      (node (ref "IC18") (pin "18") (pinfunction "FB1_18") (pintype "input"))
      (node (ref "IC18") (pin "6") (pinfunction "FB2_6") (pintype "input"))
      (node (ref "R60") (pin "1") (pinfunction "1_1") (pintype "passive"))
      (node (ref "R62") (pin "2") (pinfunction "2_2") (pintype "passive"))
    )
    (net (code "30") (name "Net-(IC18-FB3)") (class "Default")
      (node (ref "IC18") (pin "24") (pinfunction "FB4_24") (pintype "input"))
      (node (ref "IC18") (pin "31") (pinfunction "FB3_31") (pintype "input"))
      (node (ref "R65") (pin "1") (pinfunction "1_1") (pintype "passive"))
      (node (ref "R66") (pin "2") (pinfunction "2_2") (pintype "passive"))
    )
    (net (code "31") (name "Net-(IC18-SCL)") (class "Default")
      (node (ref "IC18") (pin "4") (pinfunction "SCL_4") (pintype "input"))
      (node (ref "R59") (pin "1") (pinfunction "1_1") (pintype "passive"))
    )
    (net (code "32") (name "Net-(IC18-SDA)") (class "Default")
      (node (ref "IC18") (pin "3") (pinfunction "SDA_3") (pintype "bidirectional"))
      (node (ref "R58") (pin "1") (pinfunction "1_1") (pintype "passive"))
    )
    (net (code "33") (name "Net-(IC18-SW1)") (class "Default")
      (node (ref "IC18") (pin "11") (pinfunction "SW2_11") (pintype "output"))
      (node (ref "IC18") (pin "12") (pinfunction "SW1_12") (pintype "output"))
    )
    (net (code "34") (name "Net-(IC18-VCC)") (class "Default")
      (node (ref "C99") (pin "2") (pinfunction "2_2") (pintype "passive"))
      (node (ref "IC18") (pin "25") (pinfunction "VCC_25") (pintype "power_in"))
    )
    (net (code "35") (name "Net-(IC19-FB1)") (class "Default")
      (node (ref "IC19") (pin "18") (pinfunction "FB1_18") (pintype "input"))
      (node (ref "R74") (pin "1") (pinfunction "1_1") (pintype "passive"))
      (node (ref "R76") (pin "2") (pinfunction "2_2") (pintype "passive"))
      (node (ref "R77") (pin "2") (pinfunction "2_2") (pintype "passive"))
    )
    (net (code "36") (name "Net-(IC19-FB2)") (class "Default")
      (node (ref "IC19") (pin "6") (pinfunction "FB2_6") (pintype "input"))
      (node (ref "R81") (pin "1") (pinfunction "1_1") (pintype "passive"))
      (node (ref "R82") (pin "2") (pinfunction "2_2") (pintype "passive"))
    )
    (net (code "37") (name "Net-(IC19-FB3)") (class "Default")
      (node (ref "IC19") (pin "31") (pinfunction "FB3_31") (pintype "input"))
      (node (ref "R84") (pin "1") (pinfunction "1_1") (pintype "passive"))
      (node (ref "R85") (pin "2") (pinfunction "2_2") (pintype "passive"))
    )
    (net (code "38") (name "Net-(IC19-FB4)") (class "Default")
      (node (ref "IC19") (pin "24") (pinfunction "FB4_24") (pintype "input"))
      (node (ref "R90") (pin "1") (pinfunction "1_1") (pintype "passive"))
      (node (ref "R91") (pin "2") (pinfunction "2_2") (pintype "passive"))
    )
    (net (code "39") (name "Net-(IC19-SCL)") (class "Default")
      (node (ref "IC19") (pin "4") (pinfunction "SCL_4") (pintype "input"))
      (node (ref "R73") (pin "1") (pinfunction "1_1") (pintype "passive"))
    )
    (net (code "40") (name "Net-(IC19-SDA)") (class "Default")
      (node (ref "IC19") (pin "3") (pinfunction "SDA_3") (pintype "bidirectional"))
      (node (ref "R72") (pin "1") (pinfunction "1_1") (pintype "passive"))
    )
    (net (code "41") (name "Net-(IC19-VCC)") (class "Default")
      (node (ref "C112") (pin "2") (pinfunction "2_2") (pintype "passive"))
      (node (ref "IC19") (pin "25") (pinfunction "VCC_25") (pintype "power_in"))
    )
    (net (code "42") (name "Net-(IC20A-B)") (class "Default")
      (node (ref "IC20") (pin "2") (pinfunction "B_2") (pintype "input"))
      (node (ref "R96") (pin "2") (pinfunction "2_2") (pintype "passive"))
      (node (ref "R98") (pin "2") (pinfunction "2_2") (pintype "passive"))
    )
    (net (code "43") (name "Net-(IC20A-CX)") (class "Default")
      (node (ref "C113") (pin "2") (pinfunction "2_2") (pintype "passive"))
      (node (ref "IC20") (pin "14") (pinfunction "CX_14") (pintype "passive"))
    )
    (net (code "44") (name "Net-(IC20A-CX{slash}RX)") (class "Default")
      (node (ref "C113") (pin "1") (pinfunction "1_1") (pintype "passive"))
      (node (ref "IC20") (pin "15") (pinfunction "CX/RX_15") (pintype "passive"))
      (node (ref "R95") (pin "2") (pinfunction "2_2") (pintype "passive"))
    )
    (net (code "45") (name "Net-(IC20A-Q)") (class "Default")
      (node (ref "IC20") (pin "10") (pinfunction "B_10") (pintype "input"))
      (node (ref "IC20") (pin "13") (pinfunction "Q_13") (pintype "output"))
      (node (ref "T5") (pin "2") (pinfunction "G_2") (pintype "passive"))
    )
    (net (code "46") (name "Net-(IC20A-~{CLR})") (class "Default")
      (node (ref "IC20") (pin "3") (pinfunction "~{CLR}_3") (pintype "input"))
      (node (ref "R97") (pin "2") (pinfunction "2_2") (pintype "passive"))
    )
    (net (code "47") (name "Net-(IC20B-CX)") (class "Default")
      (node (ref "C115") (pin "2") (pinfunction "2_2") (pintype "passive"))
      (node (ref "IC20") (pin "6") (pinfunction "CX_6") (pintype "passive"))
    )
    (net (code "48") (name "Net-(IC20B-CX{slash}RX)") (class "Default")
      (node (ref "C115") (pin "1") (pinfunction "1_1") (pintype "passive"))
      (node (ref "IC20") (pin "7") (pinfunction "CX/RX_7") (pintype "passive"))
      (node (ref "R99") (pin "2") (pinfunction "2_2") (pintype "passive"))
    )
    (net (code "49") (name "Net-(IC20B-~{Q})") (class "Default")
      (node (ref "IC20") (pin "12") (pinfunction "~{Q}_12") (pintype "output"))
      (node (ref "T5") (pin "5") (pinfunction "G_5") (pintype "passive"))
    )
    (net (code "50") (name "Net-(R92-Pad2)") (class "Default")
      (node (ref "R92") (pin "2") (pinfunction "2_2") (pintype "passive"))
      (node (ref "R96") (pin "1") (pinfunction "1_1") (pintype "passive"))
    )
    (net (code "51") (name "Net-(T1A-D)") (class "Default")
      (node (ref "R70") (pin "1") (pinfunction "1_1") (pintype "passive"))
      (node (ref "T1") (pin "5") (pinfunction "G_5") (pintype "passive"))
      (node (ref "T1") (pin "6") (pinfunction "D_6") (pintype "passive"))
    )
    (net (code "52") (name "Net-(T1A-G)") (class "Default")
      (node (ref "R75") (pin "2") (pinfunction "2_2") (pintype "passive"))
      (node (ref "T1") (pin "2") (pinfunction "G_2") (pintype "passive"))
    )
    (net (code "53") (name "Net-(T1B-S)") (class "Default")
      (node (ref "R67") (pin "1") (pinfunction "1_1") (pintype "passive"))
      (node (ref "R70") (pin "2") (pinfunction "2_2") (pintype "passive"))
      (node (ref "T1") (pin "4") (pinfunction "S_4") (pintype "passive"))
    )
    (net (code "54") (name "Net-(T2A-G)") (class "Default")
      (node (ref "R80") (pin "2") (pinfunction "2_2") (pintype "passive"))
      (node (ref "T2") (pin "2") (pinfunction "G_2") (pintype "passive"))
      (node (ref "T2") (pin "3") (pinfunction "D_3") (pintype "passive"))
    )
    (net (code "55") (name "Net-(T2B-S)") (class "Default")
      (node (ref "R69") (pin "1") (pinfunction "1_1") (pintype "passive"))
      (node (ref "T2") (pin "4") (pinfunction "S_4") (pintype "passive"))
    )
    (net (code "56") (name "Net-(T3A-D)") (class "Default")
      (node (ref "R88") (pin "1") (pinfunction "1_1") (pintype "passive"))
      (node (ref "T3") (pin "5") (pinfunction "G_5") (pintype "passive"))
      (node (ref "T3") (pin "6") (pinfunction "D_6") (pintype "passive"))
    )
    (net (code "57") (name "Net-(T4A-G)") (class "Default")
      (node (ref "R93") (pin "1") (pinfunction "1_1") (pintype "passive"))
      (node (ref "T4") (pin "2") (pinfunction "G_2") (pintype "passive"))
      (node (ref "T4") (pin "3") (pinfunction "D_3") (pintype "passive"))
    )
    (net (code "58") (name "P1V1") (class "Default")
      (node (ref "R71") (pin "2") (pinfunction "2_2") (pintype "passive"))
    )
    (net (code "59") (name "P1V8") (class "Default")
      (node (ref "R58") (pin "2") (pinfunction "2_2") (pintype "passive"))
      (node (ref "R59") (pin "2") (pinfunction "2_2") (pintype "passive"))
      (node (ref "R68") (pin "2") (pinfunction "2_2") (pintype "passive"))
      (node (ref "R69") (pin "2") (pinfunction "2_2") (pintype "passive"))
      (node (ref "R72") (pin "2") (pinfunction "2_2") (pintype "passive"))
      (node (ref "R73") (pin "2") (pinfunction "2_2") (pintype "passive"))
      (node (ref "R79") (pin "2") (pinfunction "2_2") (pintype "passive"))
      (node (ref "R88") (pin "2") (pinfunction "2_2") (pintype "passive"))
      (node (ref "R94") (pin "2") (pinfunction "2_2") (pintype "passive"))
    )
    (net (code "60") (name "P2V5") (class "Default")
      (node (ref "R83") (pin "2") (pinfunction "2_2") (pintype "passive"))
    )
    (net (code "61") (name "P3V3") (class "Default")
      (node (ref "IC20") (pin "16") (pinfunction "VCC_16") (pintype "power_in"))
      (node (ref "R100") (pin "1") (pinfunction "1_1") (pintype "passive"))
      (node (ref "R61") (pin "2") (pinfunction "2_2") (pintype "passive"))
      (node (ref "R87") (pin "2") (pinfunction "2_2") (pintype "passive"))
      (node (ref "R89") (pin "2") (pinfunction "2_2") (pintype "passive"))
      (node (ref "R95") (pin "1") (pinfunction "1_1") (pintype "passive"))
      (node (ref "R97") (pin "1") (pinfunction "1_1") (pintype "passive"))
      (node (ref "R99") (pin "1") (pinfunction "1_1") (pintype "passive"))
    )
    (net (code "62") (name "P5V0_SMARC") (class "Default")
      (node (ref "R57") (pin "2") (pinfunction "2_2") (pintype "passive"))
      (node (ref "R67") (pin "2") (pinfunction "2_2") (pintype "passive"))
    )
    (net (code "63") (name "P5V0_USB") (class "Default")
      (node (ref "R64") (pin "2") (pinfunction "2_2") (pintype "passive"))
      (node (ref "SW2") (pin "1") (pinfunction "1_1") (pintype "bidirectional"))
    )
    (net (code "64") (name "P12V0_KASLI") (class "Default")
      (node (ref "C106") (pin "1") (pinfunction "1_1") (pintype "passive"))
      (node (ref "C107") (pin "1") (pinfunction "1_1") (pintype "passive"))
      (node (ref "C108") (pin "2") (pinfunction "2_2") (pintype "passive"))
      (node (ref "C109") (pin "2") (pinfunction "2_2") (pintype "passive"))
      (node (ref "C93") (pin "1") (pinfunction "1_1") (pintype "passive"))
      (node (ref "C94") (pin "1") (pinfunction "1_1") (pintype "passive"))
      (node (ref "C95") (pin "2") (pinfunction "2_2") (pintype "passive"))
      (node (ref "C96") (pin "2") (pinfunction "2_2") (pintype "passive"))
      (node (ref "IC18") (pin "28") (pinfunction "VIN_28") (pintype "input"))
      (node (ref "IC18") (pin "29") (pinfunction "VIN_29") (pintype "input"))
      (node (ref "IC19") (pin "28") (pinfunction "VIN_28") (pintype "input"))
      (node (ref "IC19") (pin "29") (pinfunction "VIN_29") (pintype "input"))
      (node (ref "SW2") (pin "3") (pinfunction "3_3") (pintype "bidirectional"))
    )
    (net (code "65") (name "VCC_FAN") (class "Default")
      (node (ref "D8") (pin "1") (pinfunction "C_1") (pintype "passive"))
      (node (ref "F1") (pin "2") (pinfunction "2_2") (pintype "passive"))
      (node (ref "J2") (pin "2") (pinfunction "2_2") (pintype "bidirectional"))
      (node (ref "R86") (pin "2") (pinfunction "2_2") (pintype "passive"))
      (node (ref "R93") (pin "2") (pinfunction "2_2") (pintype "passive"))
    )
    (net (code "66") (name "unconnected-(IC19-SW1-Pad12)") (class "Default")
      (node (ref "IC19") (pin "12") (pinfunction "SW1_12") (pintype "output"))
    )
    (net (code "67") (name "unconnected-(IC19-SW2-Pad11)") (class "Default")
      (node (ref "IC19") (pin "11") (pinfunction "SW2_11") (pintype "output+no_connect"))
    )
    (net (code "68") (name "unconnected-(IC20A-~{Q}-Pad4)") (class "Default")
      (node (ref "IC20") (pin "4") (pinfunction "~{Q}_4") (pintype "output+no_connect"))
    )
    (net (code "69") (name "unconnected-(IC20B-Q-Pad5)") (class "Default")
      (node (ref "IC20") (pin "5") (pinfunction "Q_5") (pintype "output+no_connect"))
    )
  )
)
